# DS3231-RTC.net
KiCad netlist of a schematic drawn in Altium Designer
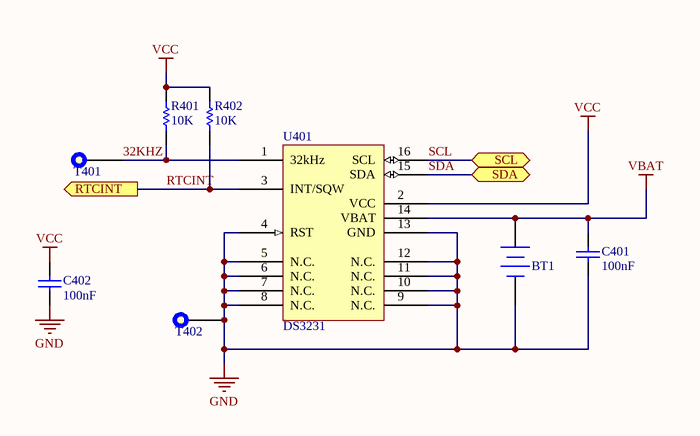
[diagram p0: DS3231-RTC.SchDoc]

(export (version "E")
  (design (tool "Eeschema 10.0.6"))
  (components
    (comp (ref "BT1")
      (value "Battery")
      (footprint "2032HOLDER")
      (description "Multicell Battery")
      (fields (field (name "PUBLISHER") "Altium Limited"))
      (libsource (lib "Miscellaneous Devices") (part "Battery"))
    )
    (comp (ref "C401")
      (value "100nF")
      (footprint "RCL 0805")
      (description "Capacitor")
      (fields (field (name "Comment") "Cap") (field (name "PUBLISHER") "Altium Limited"))
      (libsource (lib "Miscellaneous Devices") (part "Cap"))
    )
    (comp (ref "C402")
      (value "100nF")
      (footprint "RCL 0805")
      (description "Capacitor")
      (fields (field (name "Comment") "Cap") (field (name "PUBLISHER") "Altium Limited"))
      (libsource (lib "Miscellaneous Devices") (part "Cap"))
    )
    (comp (ref "R401")
      (value "10K")
      (footprint "RCL 0805")
      (description "Semiconductor Resistor")
      (fields (field (name "Comment") "Res Semi") (field (name "PUBLISHER") "Altium Limited"))
      (libsource (lib "Miscellaneous Devices") (part "Res Semi"))
    )
    (comp (ref "R402")
      (value "10K")
      (footprint "RCL 0805")
      (description "Semiconductor Resistor")
      (fields (field (name "Comment") "Res Semi") (field (name "PUBLISHER") "Altium Limited"))
      (libsource (lib "Miscellaneous Devices") (part "Res Semi"))
    )
    (comp (ref "T401")
      (value "TESTPOINT")
      (footprint "TEST POINT 1")
      (libsource (lib "MyLibrary") (part "TESTPOINT"))
    )
    (comp (ref "T402")
      (value "TESTPOINT")
      (footprint "TEST POINT 1")
      (libsource (lib "MyLibrary") (part "TESTPOINT"))
    )
    (comp (ref "U401")
      (value "DS3231")
      (footprint "WSO16_M")
      (description "Extremely Accurate I²C-Integrated RTC/TCXO/Crystal")
      (libsource (lib "MyLibrary") (part "DS3231"))
    )
  )
  (nets
    (net (code "1") (name "/32KHZ") (class "Default")
      (node (ref "R401") (pin "1") (pinfunction "1_1") (pintype "passive"))
      (node (ref "T401") (pin "1") (pinfunction "TST_1") (pintype "passive"))
      (node (ref "U401") (pin "1") (pinfunction "32kHz_1") (pintype "open_collector"))
    )
    (net (code "2") (name "/RTCINT") (class "Default")
      (node (ref "R402") (pin "1") (pinfunction "1_1") (pintype "passive"))
      (node (ref "U401") (pin "3") (pinfunction "INT/SQW_3") (pintype "open_collector"))
    )
    (net (code "3") (name "/SCL") (class "Default")
      (node (ref "U401") (pin "16") (pinfunction "SCL_16") (pintype "bidirectional"))
    )
    (net (code "4") (name "/SDA") (class "Default")
      (node (ref "U401") (pin "15") (pinfunction "SDA_15") (pintype "bidirectional"))
    )
    (net (code "5") (name "GND") (class "Default")
      (node (ref "BT1") (pin "2") (pinfunction "-_2") (pintype "passive"))
      (node (ref "C401") (pin "1") (pinfunction "1_1") (pintype "passive"))
      (node (ref "C402") (pin "1") (pinfunction "1_1") (pintype "passive"))
      (node (ref "T402") (pin "1") (pinfunction "TST_1") (pintype "passive"))
      (node (ref "U401") (pin "10") (pinfunction "N.C._10") (pintype "passive"))
      (node (ref "U401") (pin "11") (pinfunction "N.C._11") (pintype "passive"))
      (node (ref "U401") (pin "12") (pinfunction "N.C._12") (pintype "passive"))
      (node (ref "U401") (pin "13") (pinfunction "GND_13") (pintype "power_in"))
      (node (ref "U401") (pin "4") (pinfunction "RST_4") (pintype "input"))
      (node (ref "U401") (pin "5") (pinfunction "N.C._5") (pintype "passive"))
      (node (ref "U401") (pin "6") (pinfunction "N.C._6") (pintype "passive"))
      (node (ref "U401") (pin "7") (pinfunction "N.C._7") (pintype "passive"))
      (node (ref "U401") (pin "8") (pinfunction "N.C._8") (pintype "passive"))
      (node (ref "U401") (pin "9") (pinfunction "N.C._9") (pintype "passive"))
    )
    (net (code "6") (name "VBAT") (class "Default")
      (node (ref "BT1") (pin "1") (pinfunction "+_1") (pintype "passive"))
      (node (ref "C401") (pin "2") (pinfunction "2_2") (pintype "passive"))
      (node (ref "U401") (pin "14") (pinfunction "VBAT_14") (pintype "power_in"))
    )
    (net (code "7") (name "VCC") (class "Default")
      (node (ref "C402") (pin "2") (pinfunction "2_2") (pintype "passive"))
      (node (ref "R401") (pin "2") (pinfunction "2_2") (pintype "passive"))
      (node (ref "R402") (pin "2") (pinfunction "2_2") (pintype "passive"))
      (node (ref "U401") (pin "2") (pinfunction "VCC_2") (pintype "power_in"))
    )
  )
)
